# TLCduino.net
KiCad netlist of a schematic drawn in EAGLE
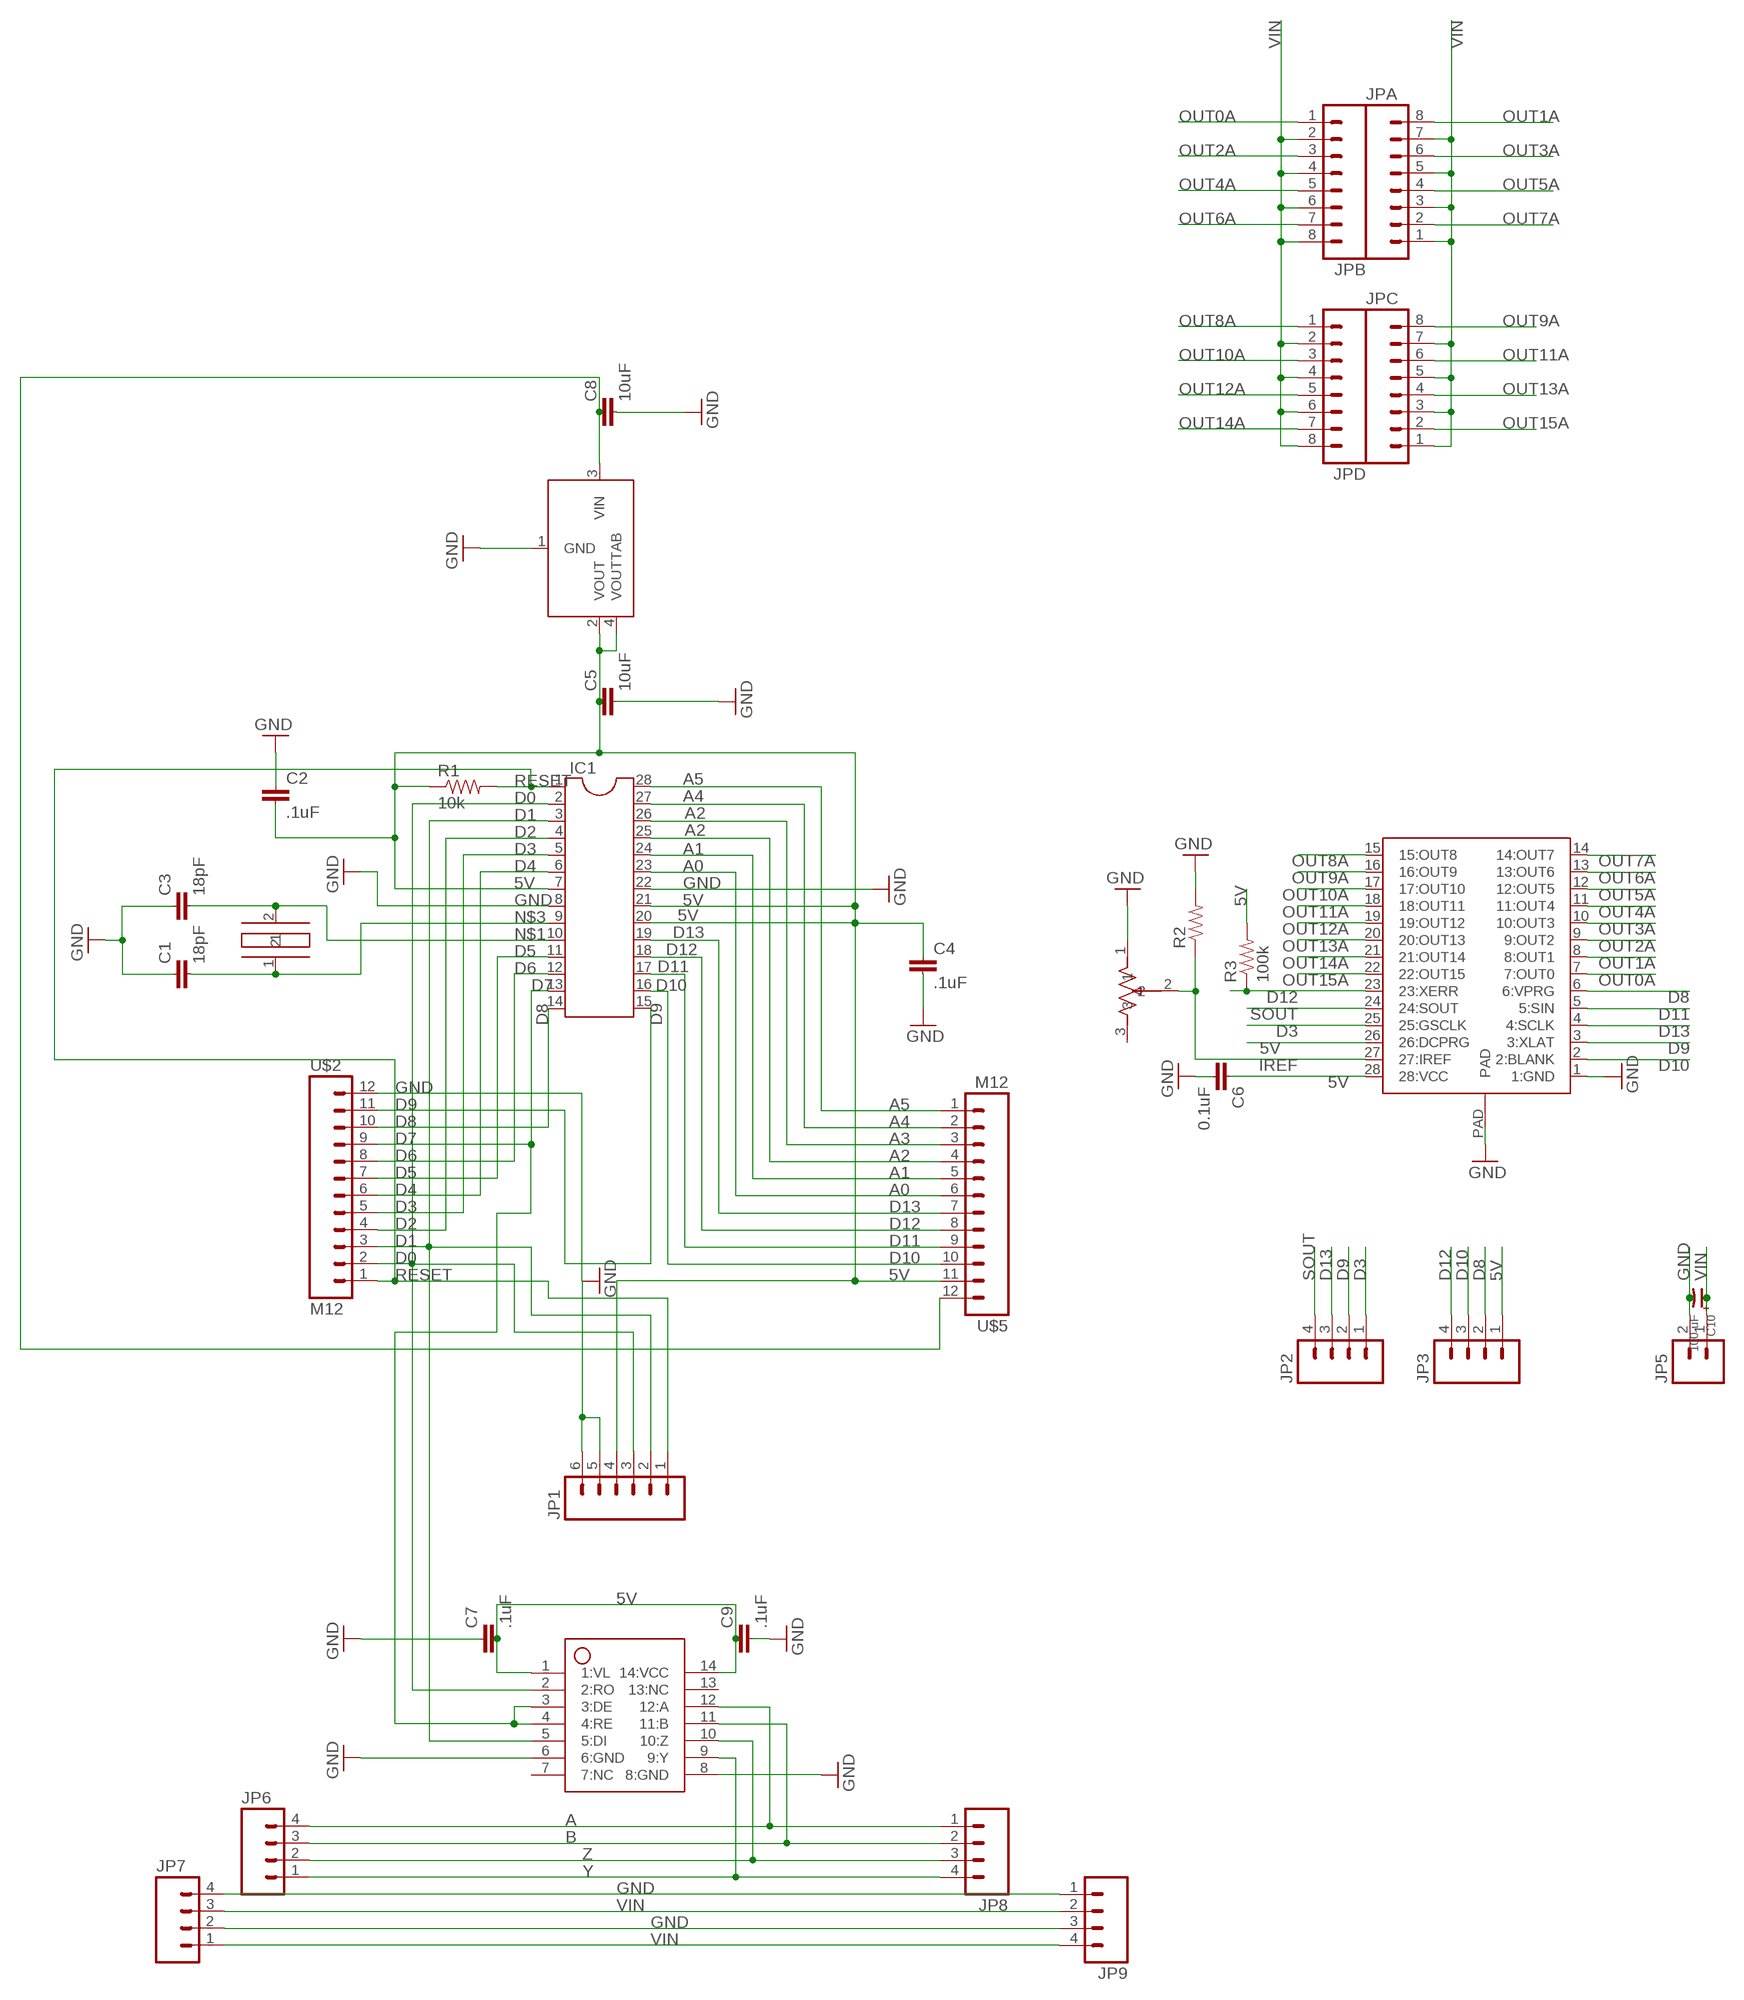
[diagram p0: schematic, sheet 1]

(export (version "E")
  (design (tool "Eeschema 10.0.6"))
  (components
    (comp (ref "5V")
      (value "ZLDO1117")
      (footprint "eagle-import:ZLDO1117")
      (libsource (lib "eagle-import") (part "ZLDO1117"))
    )
    (comp (ref "C1")
      (value "18pF")
      (footprint "eagle-import:0603-CAP")
      (libsource (lib "eagle-import") (part "CAP0603-CAP"))
    )
    (comp (ref "C2")
      (value ".1uF")
      (footprint "eagle-import:0805")
      (libsource (lib "eagle-import") (part "CAP0805"))
    )
    (comp (ref "C3")
      (value "18pF")
      (footprint "eagle-import:0603-CAP")
      (libsource (lib "eagle-import") (part "CAP0603-CAP"))
    )
    (comp (ref "C4")
      (value ".1uF")
      (footprint "eagle-import:0805")
      (libsource (lib "eagle-import") (part "CAP0805"))
    )
    (comp (ref "C5")
      (value "10uF")
      (footprint "eagle-import:1206")
      (libsource (lib "eagle-import") (part "CAP1206"))
    )
    (comp (ref "C6")
      (value "0.1uF")
      (footprint "eagle-import:0805")
      (libsource (lib "eagle-import") (part "CAP0805"))
    )
    (comp (ref "C7")
      (value ".1uF")
      (footprint "eagle-import:0805")
      (libsource (lib "eagle-import") (part "CAP0805"))
    )
    (comp (ref "C8")
      (value "10uF")
      (footprint "eagle-import:1206")
      (libsource (lib "eagle-import") (part "CAP1206"))
    )
    (comp (ref "C9")
      (value ".1uF")
      (footprint "eagle-import:0805")
      (libsource (lib "eagle-import") (part "CAP0805"))
    )
    (comp (ref "C10")
      (value "100 uF")
      (footprint "eagle-import:5X11MMCAP")
      (libsource (lib "eagle-import") (part "CAPPOL-5X11"))
    )
    (comp (ref "IC1")
      (value "DIL28-3")
      (footprint "eagle-import:DIL28-3")
      (libsource (lib "eagle-import") (part "DIL28-3"))
    )
    (comp (ref "JP1")
      (value "M06LOCK")
      (footprint "eagle-import:1X06_LOCK")
      (libsource (lib "eagle-import") (part "M06LOCK"))
    )
    (comp (ref "JP2")
      (value "M04LOCK")
      (footprint "eagle-import:1X04_LOCK")
      (libsource (lib "eagle-import") (part "M04LOCK"))
    )
    (comp (ref "JP3")
      (value "M04LOCK")
      (footprint "eagle-import:1X04_LOCK")
      (libsource (lib "eagle-import") (part "M04LOCK"))
    )
    (comp (ref "JP5")
      (value "M02LOCK")
      (footprint "eagle-import:1X02_LOCK")
      (libsource (lib "eagle-import") (part "M02LOCK"))
    )
    (comp (ref "JP6")
      (value "M04LOCK")
      (footprint "eagle-import:1X04_LOCK")
      (libsource (lib "eagle-import") (part "M04LOCK"))
    )
    (comp (ref "JP7")
      (value "M04LOCK")
      (footprint "eagle-import:1X04_LOCK")
      (libsource (lib "eagle-import") (part "M04LOCK"))
    )
    (comp (ref "JP8")
      (value "M04LOCK")
      (footprint "eagle-import:1X04_LOCK")
      (libsource (lib "eagle-import") (part "M04LOCK"))
    )
    (comp (ref "JP9")
      (value "M04LOCK")
      (footprint "eagle-import:1X04_LOCK")
      (libsource (lib "eagle-import") (part "M04LOCK"))
    )
    (comp (ref "JPA")
      (value "M08LOCK")
      (footprint "eagle-import:1X08_LOCK")
      (libsource (lib "eagle-import") (part "M08LOCK"))
    )
    (comp (ref "JPB")
      (value "M08LOCK")
      (footprint "eagle-import:1X08_LOCK")
      (libsource (lib "eagle-import") (part "M08LOCK"))
    )
    (comp (ref "JPC")
      (value "M08LOCK")
      (footprint "eagle-import:1X08_LOCK")
      (libsource (lib "eagle-import") (part "M08LOCK"))
    )
    (comp (ref "JPD")
      (value "M08LOCK")
      (footprint "eagle-import:1X08_LOCK")
      (libsource (lib "eagle-import") (part "M08LOCK"))
    )
    (comp (ref "R1")
      (value "10k")
      (footprint "eagle-import:0805")
      (libsource (lib "eagle-import") (part "RESISTOR"))
    )
    (comp (ref "R2")
      (value "RESISTOR")
      (footprint "eagle-import:0805")
      (libsource (lib "eagle-import") (part "RESISTOR"))
    )
    (comp (ref "R3")
      (value "100k")
      (footprint "eagle-import:0805")
      (libsource (lib "eagle-import") (part "RESISTOR"))
    )
    (comp (ref "U$1")
      (value "HC49US")
      (footprint "eagle-import:HC49US")
      (libsource (lib "eagle-import") (part "HC49US"))
    )
    (comp (ref "U$2")
      (value "M12")
      (footprint "eagle-import:1X12_LOCK")
      (libsource (lib "eagle-import") (part "M12LOCK"))
    )
    (comp (ref "U$3")
      (value "TLC5940")
      (footprint "eagle-import:HTSSOP-28")
      (libsource (lib "eagle-import") (part "TLC5940"))
    )
    (comp (ref "U$4")
      (value "TRIMPOTTC33X-2")
      (footprint "eagle-import:TC33X-2")
      (libsource (lib "eagle-import") (part "TRIMPOTTC33X-2"))
    )
    (comp (ref "U$5")
      (value "M12")
      (footprint "eagle-import:1X12_LOCK")
      (libsource (lib "eagle-import") (part "M12LOCK"))
    )
    (comp (ref "U$6")
      (value "MAX13432")
      (footprint "eagle-import:SO14")
      (libsource (lib "eagle-import") (part "MAX13432"))
    )
  )
  (nets
    (net (code "1") (name "/5V") (class "Default")
      (node (ref "5V") (pin "2") (pinfunction "VOUT_2") (pintype "bidirectional"))
      (node (ref "5V") (pin "4") (pinfunction "VOUTTAB_4") (pintype "bidirectional"))
      (node (ref "C2") (pin "2") (pinfunction "2_2") (pintype "passive"))
      (node (ref "C4") (pin "1") (pinfunction "1_1") (pintype "passive"))
      (node (ref "C5") (pin "1") (pinfunction "1_1") (pintype "passive"))
      (node (ref "C6") (pin "1") (pinfunction "1_1") (pintype "passive"))
      (node (ref "C7") (pin "2") (pinfunction "2_2") (pintype "passive"))
      (node (ref "C9") (pin "1") (pinfunction "1_1") (pintype "passive"))
      (node (ref "IC1") (pin "20") (pinfunction "20_20") (pintype "passive"))
      (node (ref "IC1") (pin "21") (pinfunction "21_21") (pintype "passive"))
      (node (ref "IC1") (pin "7") (pinfunction "7_7") (pintype "passive"))
      (node (ref "JP1") (pin "4") (pinfunction "4_4") (pintype "passive"))
      (node (ref "JP3") (pin "1") (pinfunction "1_1") (pintype "passive"))
      (node (ref "R1") (pin "1") (pinfunction "1_1") (pintype "passive"))
      (node (ref "R3") (pin "2") (pinfunction "2_2") (pintype "passive"))
      (node (ref "U$3") (pin "26") (pinfunction "26:DCPRG_26") (pintype "bidirectional"))
      (node (ref "U$3") (pin "28") (pinfunction "28:VCC_28") (pintype "bidirectional"))
      (node (ref "U$5") (pin "11") (pinfunction "11_11") (pintype "passive"))
      (node (ref "U$6") (pin "1") (pinfunction "1:VL_1") (pintype "bidirectional"))
      (node (ref "U$6") (pin "14") (pinfunction "14:VCC_14") (pintype "bidirectional"))
    )
    (net (code "2") (name "/A") (class "Default")
      (node (ref "JP6") (pin "4") (pinfunction "4_4") (pintype "passive"))
      (node (ref "JP8") (pin "1") (pinfunction "1_1") (pintype "passive"))
      (node (ref "U$6") (pin "12") (pinfunction "12:A_12") (pintype "bidirectional"))
    )
    (net (code "3") (name "/A0") (class "Default")
      (node (ref "IC1") (pin "23") (pinfunction "23_23") (pintype "passive"))
      (node (ref "U$5") (pin "6") (pinfunction "6_6") (pintype "passive"))
    )
    (net (code "4") (name "/A1") (class "Default")
      (node (ref "IC1") (pin "24") (pinfunction "24_24") (pintype "passive"))
      (node (ref "U$5") (pin "5") (pinfunction "5_5") (pintype "passive"))
    )
    (net (code "5") (name "/A2") (class "Default")
      (node (ref "IC1") (pin "25") (pinfunction "25_25") (pintype "passive"))
      (node (ref "U$5") (pin "4") (pinfunction "4_4") (pintype "passive"))
    )
    (net (code "6") (name "/A3") (class "Default")
      (node (ref "IC1") (pin "26") (pinfunction "26_26") (pintype "passive"))
      (node (ref "U$5") (pin "3") (pinfunction "3_3") (pintype "passive"))
    )
    (net (code "7") (name "/A4") (class "Default")
      (node (ref "IC1") (pin "27") (pinfunction "27_27") (pintype "passive"))
      (node (ref "U$5") (pin "2") (pinfunction "2_2") (pintype "passive"))
    )
    (net (code "8") (name "/A5") (class "Default")
      (node (ref "IC1") (pin "28") (pinfunction "28_28") (pintype "passive"))
      (node (ref "U$5") (pin "1") (pinfunction "1_1") (pintype "passive"))
    )
    (net (code "9") (name "/B") (class "Default")
      (node (ref "JP6") (pin "3") (pinfunction "3_3") (pintype "passive"))
      (node (ref "JP8") (pin "2") (pinfunction "2_2") (pintype "passive"))
      (node (ref "U$6") (pin "11") (pinfunction "11:B_11") (pintype "bidirectional"))
    )
    (net (code "10") (name "/D0") (class "Default")
      (node (ref "IC1") (pin "2") (pinfunction "2_2") (pintype "passive"))
      (node (ref "JP1") (pin "3") (pinfunction "3_3") (pintype "passive"))
      (node (ref "U$2") (pin "2") (pinfunction "2_2") (pintype "passive"))
      (node (ref "U$6") (pin "2") (pinfunction "2:RO_2") (pintype "bidirectional"))
    )
    (net (code "11") (name "/D1") (class "Default")
      (node (ref "IC1") (pin "3") (pinfunction "3_3") (pintype "passive"))
      (node (ref "JP1") (pin "2") (pinfunction "2_2") (pintype "passive"))
      (node (ref "U$2") (pin "3") (pinfunction "3_3") (pintype "passive"))
      (node (ref "U$6") (pin "5") (pinfunction "5:DI_5") (pintype "bidirectional"))
    )
    (net (code "12") (name "/D2") (class "Default")
      (node (ref "IC1") (pin "4") (pinfunction "4_4") (pintype "passive"))
      (node (ref "U$2") (pin "4") (pinfunction "4_4") (pintype "passive"))
    )
    (net (code "13") (name "/D3") (class "Default")
      (node (ref "IC1") (pin "5") (pinfunction "5_5") (pintype "passive"))
      (node (ref "JP2") (pin "1") (pinfunction "1_1") (pintype "passive"))
      (node (ref "U$2") (pin "5") (pinfunction "5_5") (pintype "passive"))
      (node (ref "U$3") (pin "25") (pinfunction "25:GSCLK_25") (pintype "bidirectional"))
    )
    (net (code "14") (name "/D4") (class "Default")
      (node (ref "IC1") (pin "6") (pinfunction "6_6") (pintype "passive"))
      (node (ref "U$2") (pin "6") (pinfunction "6_6") (pintype "passive"))
    )
    (net (code "15") (name "/D5") (class "Default")
      (node (ref "IC1") (pin "11") (pinfunction "11_11") (pintype "passive"))
      (node (ref "U$2") (pin "7") (pinfunction "7_7") (pintype "passive"))
    )
    (net (code "16") (name "/D6") (class "Default")
      (node (ref "IC1") (pin "12") (pinfunction "12_12") (pintype "passive"))
      (node (ref "U$2") (pin "8") (pinfunction "8_8") (pintype "passive"))
    )
    (net (code "17") (name "/D7") (class "Default")
      (node (ref "IC1") (pin "13") (pinfunction "13_13") (pintype "passive"))
      (node (ref "U$2") (pin "9") (pinfunction "9_9") (pintype "passive"))
      (node (ref "U$6") (pin "3") (pinfunction "3:DE_3") (pintype "bidirectional"))
      (node (ref "U$6") (pin "4") (pinfunction "4:RE_4") (pintype "bidirectional"))
    )
    (net (code "18") (name "/D8") (class "Default")
      (node (ref "IC1") (pin "14") (pinfunction "14_14") (pintype "passive"))
      (node (ref "JP3") (pin "2") (pinfunction "2_2") (pintype "passive"))
      (node (ref "U$2") (pin "10") (pinfunction "10_10") (pintype "passive"))
      (node (ref "U$3") (pin "6") (pinfunction "6:VPRG_6") (pintype "bidirectional"))
    )
    (net (code "19") (name "/D9") (class "Default")
      (node (ref "IC1") (pin "15") (pinfunction "15_15") (pintype "passive"))
      (node (ref "JP2") (pin "2") (pinfunction "2_2") (pintype "passive"))
      (node (ref "U$2") (pin "11") (pinfunction "11_11") (pintype "passive"))
      (node (ref "U$3") (pin "3") (pinfunction "3:XLAT_3") (pintype "bidirectional"))
    )
    (net (code "20") (name "/D10") (class "Default")
      (node (ref "IC1") (pin "16") (pinfunction "16_16") (pintype "passive"))
      (node (ref "JP3") (pin "3") (pinfunction "3_3") (pintype "passive"))
      (node (ref "U$3") (pin "2") (pinfunction "2:BLANK_2") (pintype "bidirectional"))
      (node (ref "U$5") (pin "10") (pinfunction "10_10") (pintype "passive"))
    )
    (net (code "21") (name "/D11") (class "Default")
      (node (ref "IC1") (pin "17") (pinfunction "17_17") (pintype "passive"))
      (node (ref "U$3") (pin "5") (pinfunction "5:SIN_5") (pintype "bidirectional"))
      (node (ref "U$5") (pin "9") (pinfunction "9_9") (pintype "passive"))
    )
    (net (code "22") (name "/D12") (class "Default")
      (node (ref "IC1") (pin "18") (pinfunction "18_18") (pintype "passive"))
      (node (ref "JP3") (pin "4") (pinfunction "4_4") (pintype "passive"))
      (node (ref "R3") (pin "1") (pinfunction "1_1") (pintype "passive"))
      (node (ref "U$3") (pin "23") (pinfunction "23:XERR_23") (pintype "bidirectional"))
      (node (ref "U$5") (pin "8") (pinfunction "8_8") (pintype "passive"))
    )
    (net (code "23") (name "/D13") (class "Default")
      (node (ref "IC1") (pin "19") (pinfunction "19_19") (pintype "passive"))
      (node (ref "JP2") (pin "3") (pinfunction "3_3") (pintype "passive"))
      (node (ref "U$3") (pin "4") (pinfunction "4:SCLK_4") (pintype "bidirectional"))
      (node (ref "U$5") (pin "7") (pinfunction "7_7") (pintype "passive"))
    )
    (net (code "24") (name "/IREF") (class "Default")
      (node (ref "R2") (pin "1") (pinfunction "1_1") (pintype "passive"))
      (node (ref "U$3") (pin "27") (pinfunction "27:IREF_27") (pintype "bidirectional"))
      (node (ref "U$4") (pin "2") (pinfunction "2_2") (pintype "bidirectional"))
    )
    (net (code "25") (name "/N$1") (class "Default")
      (node (ref "C3") (pin "2") (pinfunction "2_2") (pintype "passive"))
      (node (ref "IC1") (pin "10") (pinfunction "10_10") (pintype "passive"))
      (node (ref "U$1") (pin "2") (pinfunction "2_2") (pintype "bidirectional"))
    )
    (net (code "26") (name "/N$3") (class "Default")
      (node (ref "C1") (pin "2") (pinfunction "2_2") (pintype "passive"))
      (node (ref "IC1") (pin "9") (pinfunction "9_9") (pintype "passive"))
      (node (ref "U$1") (pin "1") (pinfunction "1_1") (pintype "bidirectional"))
    )
    (net (code "27") (name "/OUT0A") (class "Default")
      (node (ref "JPB") (pin "1") (pinfunction "1_1") (pintype "passive"))
      (node (ref "U$3") (pin "7") (pinfunction "7:OUT0_7") (pintype "bidirectional"))
    )
    (net (code "28") (name "/OUT1A") (class "Default")
      (node (ref "JPA") (pin "8") (pinfunction "8_8") (pintype "passive"))
      (node (ref "U$3") (pin "8") (pinfunction "8:OUT1_8") (pintype "bidirectional"))
    )
    (net (code "29") (name "/OUT2A") (class "Default")
      (node (ref "JPB") (pin "3") (pinfunction "3_3") (pintype "passive"))
      (node (ref "U$3") (pin "9") (pinfunction "9:OUT2_9") (pintype "bidirectional"))
    )
    (net (code "30") (name "/OUT3A") (class "Default")
      (node (ref "JPA") (pin "6") (pinfunction "6_6") (pintype "passive"))
      (node (ref "U$3") (pin "10") (pinfunction "10:OUT3_10") (pintype "bidirectional"))
    )
    (net (code "31") (name "/OUT4A") (class "Default")
      (node (ref "JPB") (pin "5") (pinfunction "5_5") (pintype "passive"))
      (node (ref "U$3") (pin "11") (pinfunction "11:OUT4_11") (pintype "bidirectional"))
    )
    (net (code "32") (name "/OUT5A") (class "Default")
      (node (ref "JPA") (pin "4") (pinfunction "4_4") (pintype "passive"))
      (node (ref "U$3") (pin "12") (pinfunction "12:OUT5_12") (pintype "bidirectional"))
    )
    (net (code "33") (name "/OUT6A") (class "Default")
      (node (ref "JPB") (pin "7") (pinfunction "7_7") (pintype "passive"))
      (node (ref "U$3") (pin "13") (pinfunction "13:OUT6_13") (pintype "bidirectional"))
    )
    (net (code "34") (name "/OUT7A") (class "Default")
      (node (ref "JPA") (pin "2") (pinfunction "2_2") (pintype "passive"))
      (node (ref "U$3") (pin "14") (pinfunction "14:OUT7_14") (pintype "bidirectional"))
    )
    (net (code "35") (name "/OUT8A") (class "Default")
      (node (ref "JPD") (pin "1") (pinfunction "1_1") (pintype "passive"))
      (node (ref "U$3") (pin "15") (pinfunction "15:OUT8_15") (pintype "bidirectional"))
    )
    (net (code "36") (name "/OUT9A") (class "Default")
      (node (ref "JPC") (pin "8") (pinfunction "8_8") (pintype "passive"))
      (node (ref "U$3") (pin "16") (pinfunction "16:OUT9_16") (pintype "bidirectional"))
    )
    (net (code "37") (name "/OUT10A") (class "Default")
      (node (ref "JPD") (pin "3") (pinfunction "3_3") (pintype "passive"))
      (node (ref "U$3") (pin "17") (pinfunction "17:OUT10_17") (pintype "bidirectional"))
    )
    (net (code "38") (name "/OUT11A") (class "Default")
      (node (ref "JPC") (pin "6") (pinfunction "6_6") (pintype "passive"))
      (node (ref "U$3") (pin "18") (pinfunction "18:OUT11_18") (pintype "bidirectional"))
    )
    (net (code "39") (name "/OUT12A") (class "Default")
      (node (ref "JPD") (pin "5") (pinfunction "5_5") (pintype "passive"))
      (node (ref "U$3") (pin "19") (pinfunction "19:OUT12_19") (pintype "bidirectional"))
    )
    (net (code "40") (name "/OUT13A") (class "Default")
      (node (ref "JPC") (pin "4") (pinfunction "4_4") (pintype "passive"))
      (node (ref "U$3") (pin "20") (pinfunction "20:OUT13_20") (pintype "bidirectional"))
    )
    (net (code "41") (name "/OUT14A") (class "Default")
      (node (ref "JPD") (pin "7") (pinfunction "7_7") (pintype "passive"))
      (node (ref "U$3") (pin "21") (pinfunction "21:OUT14_21") (pintype "bidirectional"))
    )
    (net (code "42") (name "/OUT15A") (class "Default")
      (node (ref "JPC") (pin "2") (pinfunction "2_2") (pintype "passive"))
      (node (ref "U$3") (pin "22") (pinfunction "22:OUT15_22") (pintype "bidirectional"))
    )
    (net (code "43") (name "/RESET") (class "Default")
      (node (ref "IC1") (pin "1") (pinfunction "1_1") (pintype "passive"))
      (node (ref "JP1") (pin "1") (pinfunction "1_1") (pintype "passive"))
      (node (ref "R1") (pin "2") (pinfunction "2_2") (pintype "passive"))
      (node (ref "U$2") (pin "1") (pinfunction "1_1") (pintype "passive"))
    )
    (net (code "44") (name "/SOUT") (class "Default")
      (node (ref "JP2") (pin "4") (pinfunction "4_4") (pintype "passive"))
      (node (ref "U$3") (pin "24") (pinfunction "24:SOUT_24") (pintype "bidirectional"))
    )
    (net (code "45") (name "/VIN") (class "Default")
      (node (ref "5V") (pin "3") (pinfunction "VIN_3") (pintype "bidirectional"))
      (node (ref "C10") (pin "+") (pinfunction "+_+") (pintype "bidirectional"))
      (node (ref "C8") (pin "1") (pinfunction "1_1") (pintype "passive"))
      (node (ref "JP5") (pin "1") (pinfunction "1_1") (pintype "passive"))
      (node (ref "JP7") (pin "1") (pinfunction "1_1") (pintype "passive"))
      (node (ref "JP7") (pin "3") (pinfunction "3_3") (pintype "passive"))
      (node (ref "JP9") (pin "2") (pinfunction "2_2") (pintype "passive"))
      (node (ref "JP9") (pin "4") (pinfunction "4_4") (pintype "passive"))
      (node (ref "JPA") (pin "1") (pinfunction "1_1") (pintype "passive"))
      (node (ref "JPA") (pin "3") (pinfunction "3_3") (pintype "passive"))
      (node (ref "JPA") (pin "5") (pinfunction "5_5") (pintype "passive"))
      (node (ref "JPA") (pin "7") (pinfunction "7_7") (pintype "passive"))
      (node (ref "JPB") (pin "2") (pinfunction "2_2") (pintype "passive"))
      (node (ref "JPB") (pin "4") (pinfunction "4_4") (pintype "passive"))
      (node (ref "JPB") (pin "6") (pinfunction "6_6") (pintype "passive"))
      (node (ref "JPB") (pin "8") (pinfunction "8_8") (pintype "passive"))
      (node (ref "JPC") (pin "1") (pinfunction "1_1") (pintype "passive"))
      (node (ref "JPC") (pin "3") (pinfunction "3_3") (pintype "passive"))
      (node (ref "JPC") (pin "5") (pinfunction "5_5") (pintype "passive"))
      (node (ref "JPC") (pin "7") (pinfunction "7_7") (pintype "passive"))
      (node (ref "JPD") (pin "2") (pinfunction "2_2") (pintype "passive"))
      (node (ref "JPD") (pin "4") (pinfunction "4_4") (pintype "passive"))
      (node (ref "JPD") (pin "6") (pinfunction "6_6") (pintype "passive"))
      (node (ref "JPD") (pin "8") (pinfunction "8_8") (pintype "passive"))
      (node (ref "U$5") (pin "12") (pinfunction "12_12") (pintype "passive"))
    )
    (net (code "46") (name "/Y") (class "Default")
      (node (ref "JP6") (pin "1") (pinfunction "1_1") (pintype "passive"))
      (node (ref "JP8") (pin "4") (pinfunction "4_4") (pintype "passive"))
      (node (ref "U$6") (pin "9") (pinfunction "9:Y_9") (pintype "bidirectional"))
    )
    (net (code "47") (name "/Z") (class "Default")
      (node (ref "JP6") (pin "2") (pinfunction "2_2") (pintype "passive"))
      (node (ref "JP8") (pin "3") (pinfunction "3_3") (pintype "passive"))
      (node (ref "U$6") (pin "10") (pinfunction "10:Z_10") (pintype "bidirectional"))
    )
    (net (code "48") (name "GND") (class "Default")
      (node (ref "5V") (pin "1") (pinfunction "GND_1") (pintype "bidirectional"))
      (node (ref "C1") (pin "1") (pinfunction "1_1") (pintype "passive"))
      (node (ref "C10") (pin "-") (pinfunction "-_-") (pintype "bidirectional"))
      (node (ref "C2") (pin "1") (pinfunction "1_1") (pintype "passive"))
      (node (ref "C3") (pin "1") (pinfunction "1_1") (pintype "passive"))
      (node (ref "C4") (pin "2") (pinfunction "2_2") (pintype "passive"))
      (node (ref "C5") (pin "2") (pinfunction "2_2") (pintype "passive"))
      (node (ref "C6") (pin "2") (pinfunction "2_2") (pintype "passive"))
      (node (ref "C7") (pin "1") (pinfunction "1_1") (pintype "passive"))
      (node (ref "C8") (pin "2") (pinfunction "2_2") (pintype "passive"))
      (node (ref "C9") (pin "2") (pinfunction "2_2") (pintype "passive"))
      (node (ref "IC1") (pin "22") (pinfunction "22_22") (pintype "passive"))
      (node (ref "IC1") (pin "8") (pinfunction "8_8") (pintype "passive"))
      (node (ref "JP1") (pin "5") (pinfunction "5_5") (pintype "passive"))
      (node (ref "JP1") (pin "6") (pinfunction "6_6") (pintype "passive"))
      (node (ref "JP5") (pin "2") (pinfunction "2_2") (pintype "passive"))
      (node (ref "JP7") (pin "2") (pinfunction "2_2") (pintype "passive"))
      (node (ref "JP7") (pin "4") (pinfunction "4_4") (pintype "passive"))
      (node (ref "JP9") (pin "1") (pinfunction "1_1") (pintype "passive"))
      (node (ref "JP9") (pin "3") (pinfunction "3_3") (pintype "passive"))
      (node (ref "R2") (pin "2") (pinfunction "2_2") (pintype "passive"))
      (node (ref "U$2") (pin "12") (pinfunction "12_12") (pintype "passive"))
      (node (ref "U$3") (pin "1") (pinfunction "1:GND_1") (pintype "bidirectional"))
      (node (ref "U$3") (pin "PAD") (pinfunction "PAD_PAD") (pintype "bidirectional"))
      (node (ref "U$4") (pin "1") (pinfunction "1_1") (pintype "bidirectional"))
      (node (ref "U$6") (pin "6") (pinfunction "6:GND_6") (pintype "bidirectional"))
      (node (ref "U$6") (pin "8") (pinfunction "8:GND_8") (pintype "bidirectional"))
    )
    (net (code "49") (name "unconnected-(U$4-Pad3)") (class "Default")
      (node (ref "U$4") (pin "3") (pinfunction "3_3") (pintype "bidirectional"))
    )
    (net (code "50") (name "unconnected-(U$6-7:NC-Pad7)") (class "Default")
      (node (ref "U$6") (pin "7") (pinfunction "7:NC_7") (pintype "bidirectional"))
    )
    (net (code "51") (name "unconnected-(U$6-13:NC-Pad13)") (class "Default")
      (node (ref "U$6") (pin "13") (pinfunction "13:NC_13") (pintype "bidirectional"))
    )
  )
)
